# Stir_Plate_Schem.net
KiCad netlist of a schematic drawn in EAGLE
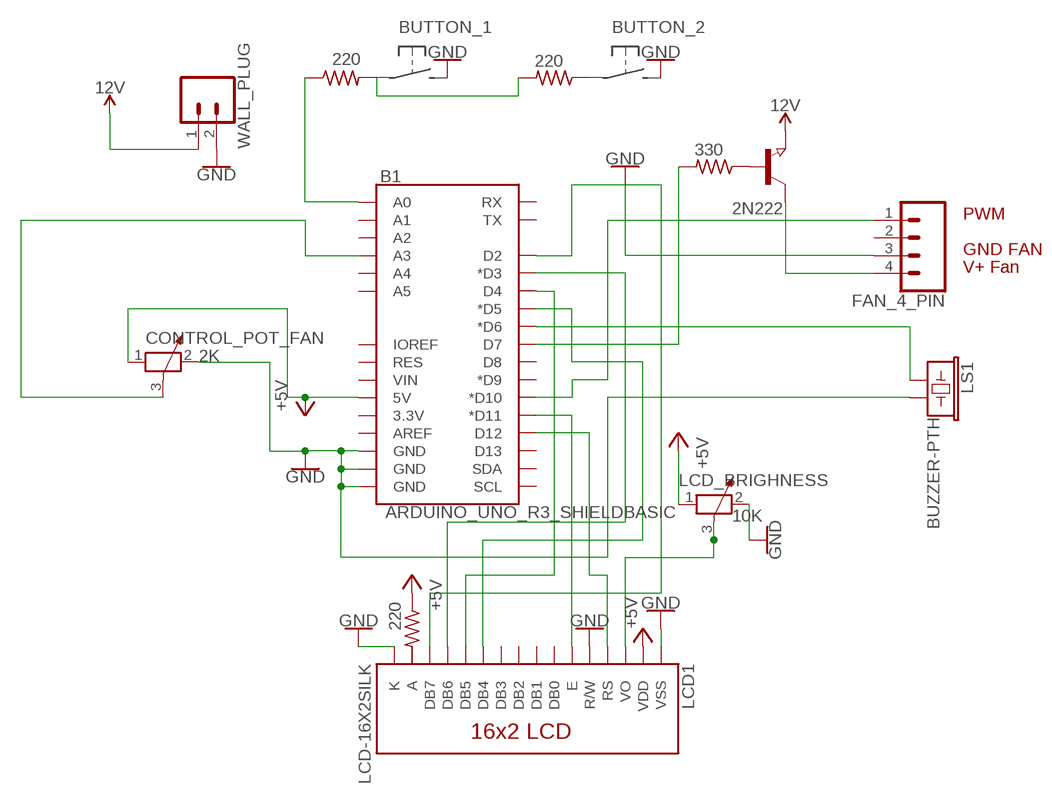
[diagram p0: schematic, sheet 1]

(export (version "E")
  (design (tool "Eeschema 10.0.6"))
  (components
    (comp (ref "B1")
      (value "ARDUINO_UNO_R3_SHIELDBASIC")
      (footprint "eagle-import:UNO_R3_SHIELD")
      (libsource (lib "eagle-import") (part "ARDUINO_UNO_R3_SHIELDBASIC"))
    )
    (comp (ref "CONTROL_POT_FAN")
      (value "2K")
      (footprint "eagle-import:PT-10")
      (libsource (lib "eagle-import") (part "POTENTIOMETER_PT-10"))
    )
    (comp (ref "FAN_4_PIN")
      (value "CONN_04")
      (footprint "eagle-import:1X04")
      (libsource (lib "eagle-import") (part "CONN_04"))
    )
    (comp (ref "LCD1")
      (value "LCD-16X2SILK")
      (footprint "eagle-import:LCD-16X2")
      (libsource (lib "eagle-import") (part "LCD-16X2SILK"))
    )
    (comp (ref "LCD_BRIGHNESS")
      (value "10K")
      (footprint "eagle-import:PT-10")
      (libsource (lib "eagle-import") (part "POTENTIOMETER_PT-10"))
    )
    (comp (ref "LS1")
      (value "BUZZER-PTH")
      (footprint "eagle-import:BUZZER-12MM")
      (libsource (lib "eagle-import") (part "BUZZER-PTH"))
    )
    (comp (ref "Q1")
      (value "2N222")
      (footprint "eagle-import:SOT23W")
      (libsource (lib "eagle-import") (part "NPN-TRANSISTOR_SOT23W"))
    )
    (comp (ref "R1")
      (value "220")
      (footprint "eagle-import:0204V")
      (libsource (lib "eagle-import") (part "R-US_0204/2V"))
    )
    (comp (ref "R2")
      (value "220")
      (footprint "eagle-import:0204V")
      (libsource (lib "eagle-import") (part "R-US_0204/2V"))
    )
    (comp (ref "R3")
      (value "220")
      (footprint "eagle-import:0204V")
      (libsource (lib "eagle-import") (part "R-US_0204/2V"))
    )
    (comp (ref "R4")
      (value "330")
      (footprint "eagle-import:0204V")
      (libsource (lib "eagle-import") (part "R-US_0204/2V"))
    )
    (comp (ref "WALL_PLUG")
      (value "CONN_02")
      (footprint "eagle-import:1X02")
      (libsource (lib "eagle-import") (part "CONN_02"))
    )
  )
  (nets
    (net (code "1") (name "+5V") (class "Default")
      (node (ref "B1") (pin "5V") (pinfunction "5V_5V") (pintype "bidirectional"))
      (node (ref "CONTROL_POT_FAN") (pin "1") (pinfunction "1_1") (pintype "passive"))
      (node (ref "LCD1") (pin "2") (pinfunction "VDD_2") (pintype "power_in"))
      (node (ref "LCD_BRIGHNESS") (pin "1") (pinfunction "1_1") (pintype "passive"))
      (node (ref "R1") (pin "1") (pinfunction "1_1") (pintype "passive"))
    )
    (net (code "2") (name "/A") (class "Default")
      (node (ref "LCD1") (pin "15") (pinfunction "A_15") (pintype "power_in"))
    )
    (net (code "3") (name "12V") (class "Default")
      (node (ref "Q1") (pin "3") (pinfunction "E_3") (pintype "passive"))
      (node (ref "WALL_PLUG") (pin "1") (pinfunction "1_1") (pintype "passive"))
    )
    (net (code "4") (name "GND") (class "Default")
      (node (ref "B1") (pin "GND@0") (pinfunction "GND_GND@0") (pintype "bidirectional"))
      (node (ref "B1") (pin "GND@1") (pinfunction "GND_GND@1") (pintype "bidirectional"))
      (node (ref "B1") (pin "GND@2") (pinfunction "GND_GND@2") (pintype "bidirectional"))
      (node (ref "CONTROL_POT_FAN") (pin "2") (pinfunction "2_2") (pintype "passive"))
      (node (ref "FAN_4_PIN") (pin "3") (pinfunction "3_3") (pintype "passive"))
      (node (ref "LCD1") (pin "1") (pinfunction "VSS_1") (pintype "power_in"))
      (node (ref "LCD1") (pin "16") (pinfunction "K_16") (pintype "power_in"))
      (node (ref "LCD1") (pin "5") (pinfunction "R/W_5") (pintype "input"))
      (node (ref "LCD_BRIGHNESS") (pin "2") (pinfunction "2_2") (pintype "passive"))
      (node (ref "LS1") (pin "-") (pinfunction "2_-") (pintype "passive"))
      (node (ref "WALL_PLUG") (pin "2") (pinfunction "2_2") (pintype "passive"))
    )
    (net (code "5") (name "Net-(B1-*D3)") (class "Default")
      (node (ref "B1") (pin "D3") (pinfunction "*D3_D3") (pintype "bidirectional"))
      (node (ref "LCD1") (pin "13") (pinfunction "DB6_13") (pintype "bidirectional"))
    )
    (net (code "6") (name "Net-(B1-*D5)") (class "Default")
      (node (ref "B1") (pin "D5") (pinfunction "*D5_D5") (pintype "bidirectional"))
      (node (ref "LCD1") (pin "11") (pinfunction "DB4_11") (pintype "bidirectional"))
    )
    (net (code "7") (name "Net-(B1-*D6)") (class "Default")
      (node (ref "B1") (pin "D6") (pinfunction "*D6_D6") (pintype "bidirectional"))
      (node (ref "LS1") (pin "+") (pinfunction "1_+") (pintype "passive"))
    )
    (net (code "8") (name "Net-(B1-*D10)") (class "Default")
      (node (ref "B1") (pin "D10") (pinfunction "*D10_D10") (pintype "bidirectional"))
      (node (ref "FAN_4_PIN") (pin "1") (pinfunction "1_1") (pintype "passive"))
    )
    (net (code "9") (name "Net-(B1-*D11)") (class "Default")
      (node (ref "B1") (pin "D11") (pinfunction "*D11_D11") (pintype "bidirectional"))
      (node (ref "LCD1") (pin "6") (pinfunction "E_6") (pintype "input"))
    )
    (net (code "10") (name "Net-(B1-PadA0)") (class "Default")
      (node (ref "B1") (pin "A0") (pinfunction "A0_A0") (pintype "bidirectional"))
      (node (ref "R2") (pin "1") (pinfunction "1_1") (pintype "passive"))
    )
    (net (code "11") (name "Net-(B1-PadA3)") (class "Default")
      (node (ref "B1") (pin "A3") (pinfunction "A3_A3") (pintype "bidirectional"))
      (node (ref "CONTROL_POT_FAN") (pin "3") (pinfunction "3_3") (pintype "passive"))
    )
    (net (code "12") (name "Net-(B1-PadD7)") (class "Default")
      (node (ref "B1") (pin "D7") (pinfunction "D7_D7") (pintype "bidirectional"))
      (node (ref "R4") (pin "2") (pinfunction "2_2") (pintype "passive"))
    )
    (net (code "13") (name "Net-(LCD1-DB5)") (class "Default")
      (node (ref "B1") (pin "D4") (pinfunction "D4_D4") (pintype "bidirectional"))
      (node (ref "LCD1") (pin "12") (pinfunction "DB5_12") (pintype "bidirectional"))
    )
    (net (code "14") (name "Net-(LCD1-DB7)") (class "Default")
      (node (ref "B1") (pin "D2") (pinfunction "D2_D2") (pintype "bidirectional"))
      (node (ref "LCD1") (pin "14") (pinfunction "DB7_14") (pintype "bidirectional"))
    )
    (net (code "15") (name "Net-(LCD1-RS)") (class "Default")
      (node (ref "B1") (pin "D12") (pinfunction "D12_D12") (pintype "bidirectional"))
      (node (ref "LCD1") (pin "4") (pinfunction "RS_4") (pintype "input"))
    )
    (net (code "16") (name "Net-(LCD1-VO)") (class "Default")
      (node (ref "LCD1") (pin "3") (pinfunction "VO_3") (pintype "bidirectional"))
      (node (ref "LCD_BRIGHNESS") (pin "3") (pinfunction "3_3") (pintype "passive"))
    )
    (net (code "17") (name "Net-(Q1-B)") (class "Default")
      (node (ref "Q1") (pin "1") (pinfunction "B_1") (pintype "passive"))
      (node (ref "R4") (pin "1") (pinfunction "1_1") (pintype "passive"))
    )
    (net (code "18") (name "Net-(Q1-C)") (class "Default")
      (node (ref "FAN_4_PIN") (pin "4") (pinfunction "4_4") (pintype "passive"))
      (node (ref "Q1") (pin "2") (pinfunction "C_2") (pintype "passive"))
    )
    (net (code "19") (name "Net-(R2-Pad2)") (class "Default")
      (node (ref "R2") (pin "2") (pinfunction "2_2") (pintype "passive"))
      (node (ref "R3") (pin "2") (pinfunction "2_2") (pintype "passive"))
    )
    (net (code "20") (name "unconnected-(B1-*D9-PadD9)") (class "Default")
      (node (ref "B1") (pin "D9") (pinfunction "*D9_D9") (pintype "bidirectional"))
    )
    (net (code "21") (name "unconnected-(B1-Pad3.3V)") (class "Default")
      (node (ref "B1") (pin "3.3V") (pinfunction "3.3V_3.3V") (pintype "bidirectional"))
    )
    (net (code "22") (name "unconnected-(B1-PadA1)") (class "Default")
      (node (ref "B1") (pin "A1") (pinfunction "A1_A1") (pintype "bidirectional"))
    )
    (net (code "23") (name "unconnected-(B1-PadA2)") (class "Default")
      (node (ref "B1") (pin "A2") (pinfunction "A2_A2") (pintype "bidirectional"))
    )
    (net (code "24") (name "unconnected-(B1-PadA4)") (class "Default")
      (node (ref "B1") (pin "A4") (pinfunction "A4_A4") (pintype "bidirectional"))
    )
    (net (code "25") (name "unconnected-(B1-PadA5)") (class "Default")
      (node (ref "B1") (pin "A5") (pinfunction "A5_A5") (pintype "bidirectional"))
    )
    (net (code "26") (name "unconnected-(B1-PadAREF)") (class "Default")
      (node (ref "B1") (pin "AREF") (pinfunction "AREF_AREF") (pintype "bidirectional"))
    )
    (net (code "27") (name "unconnected-(B1-PadD8)") (class "Default")
      (node (ref "B1") (pin "D8") (pinfunction "D8_D8") (pintype "bidirectional"))
    )
    (net (code "28") (name "unconnected-(B1-PadD13)") (class "Default")
      (node (ref "B1") (pin "D13") (pinfunction "D13_D13") (pintype "bidirectional"))
    )
    (net (code "29") (name "unconnected-(B1-PadIOREF)") (class "Default")
      (node (ref "B1") (pin "IOREF") (pinfunction "IOREF_IOREF") (pintype "bidirectional"))
    )
    (net (code "30") (name "unconnected-(B1-PadRES)") (class "Default")
      (node (ref "B1") (pin "RES") (pinfunction "RES_RES") (pintype "bidirectional"))
    )
    (net (code "31") (name "unconnected-(B1-PadRX)") (class "Default")
      (node (ref "B1") (pin "RX") (pinfunction "RX_RX") (pintype "bidirectional"))
    )
    (net (code "32") (name "unconnected-(B1-PadSCL)") (class "Default")
      (node (ref "B1") (pin "SCL") (pinfunction "SCL_SCL") (pintype "bidirectional"))
    )
    (net (code "33") (name "unconnected-(B1-PadSDA)") (class "Default")
      (node (ref "B1") (pin "SDA") (pinfunction "SDA_SDA") (pintype "bidirectional"))
    )
    (net (code "34") (name "unconnected-(B1-PadTX)") (class "Default")
      (node (ref "B1") (pin "TX") (pinfunction "TX_TX") (pintype "bidirectional"))
    )
    (net (code "35") (name "unconnected-(B1-PadVIN)") (class "Default")
      (node (ref "B1") (pin "VIN") (pinfunction "VIN_VIN") (pintype "bidirectional"))
    )
    (net (code "36") (name "unconnected-(FAN_4_PIN-Pad2)") (class "Default")
      (node (ref "FAN_4_PIN") (pin "2") (pinfunction "2_2") (pintype "passive"))
    )
    (net (code "37") (name "unconnected-(LCD1-DB0-Pad7)") (class "Default")
      (node (ref "LCD1") (pin "7") (pinfunction "DB0_7") (pintype "bidirectional"))
    )
    (net (code "38") (name "unconnected-(LCD1-DB1-Pad8)") (class "Default")
      (node (ref "LCD1") (pin "8") (pinfunction "DB1_8") (pintype "bidirectional"))
    )
    (net (code "39") (name "unconnected-(LCD1-DB2-Pad9)") (class "Default")
      (node (ref "LCD1") (pin "9") (pinfunction "DB2_9") (pintype "bidirectional"))
    )
    (net (code "40") (name "unconnected-(LCD1-DB3-Pad10)") (class "Default")
      (node (ref "LCD1") (pin "10") (pinfunction "DB3_10") (pintype "bidirectional"))
    )
    (net (code "41") (name "unconnected-(R1-Pad2)") (class "Default")
      (node (ref "R1") (pin "2") (pinfunction "2_2") (pintype "passive"))
    )
    (net (code "42") (name "unconnected-(R3-Pad1)") (class "Default")
      (node (ref "R3") (pin "1") (pinfunction "1_1") (pintype "passive"))
    )
  )
)
